# XmasRings.net
KiCad netlist of a schematic drawn in EAGLE
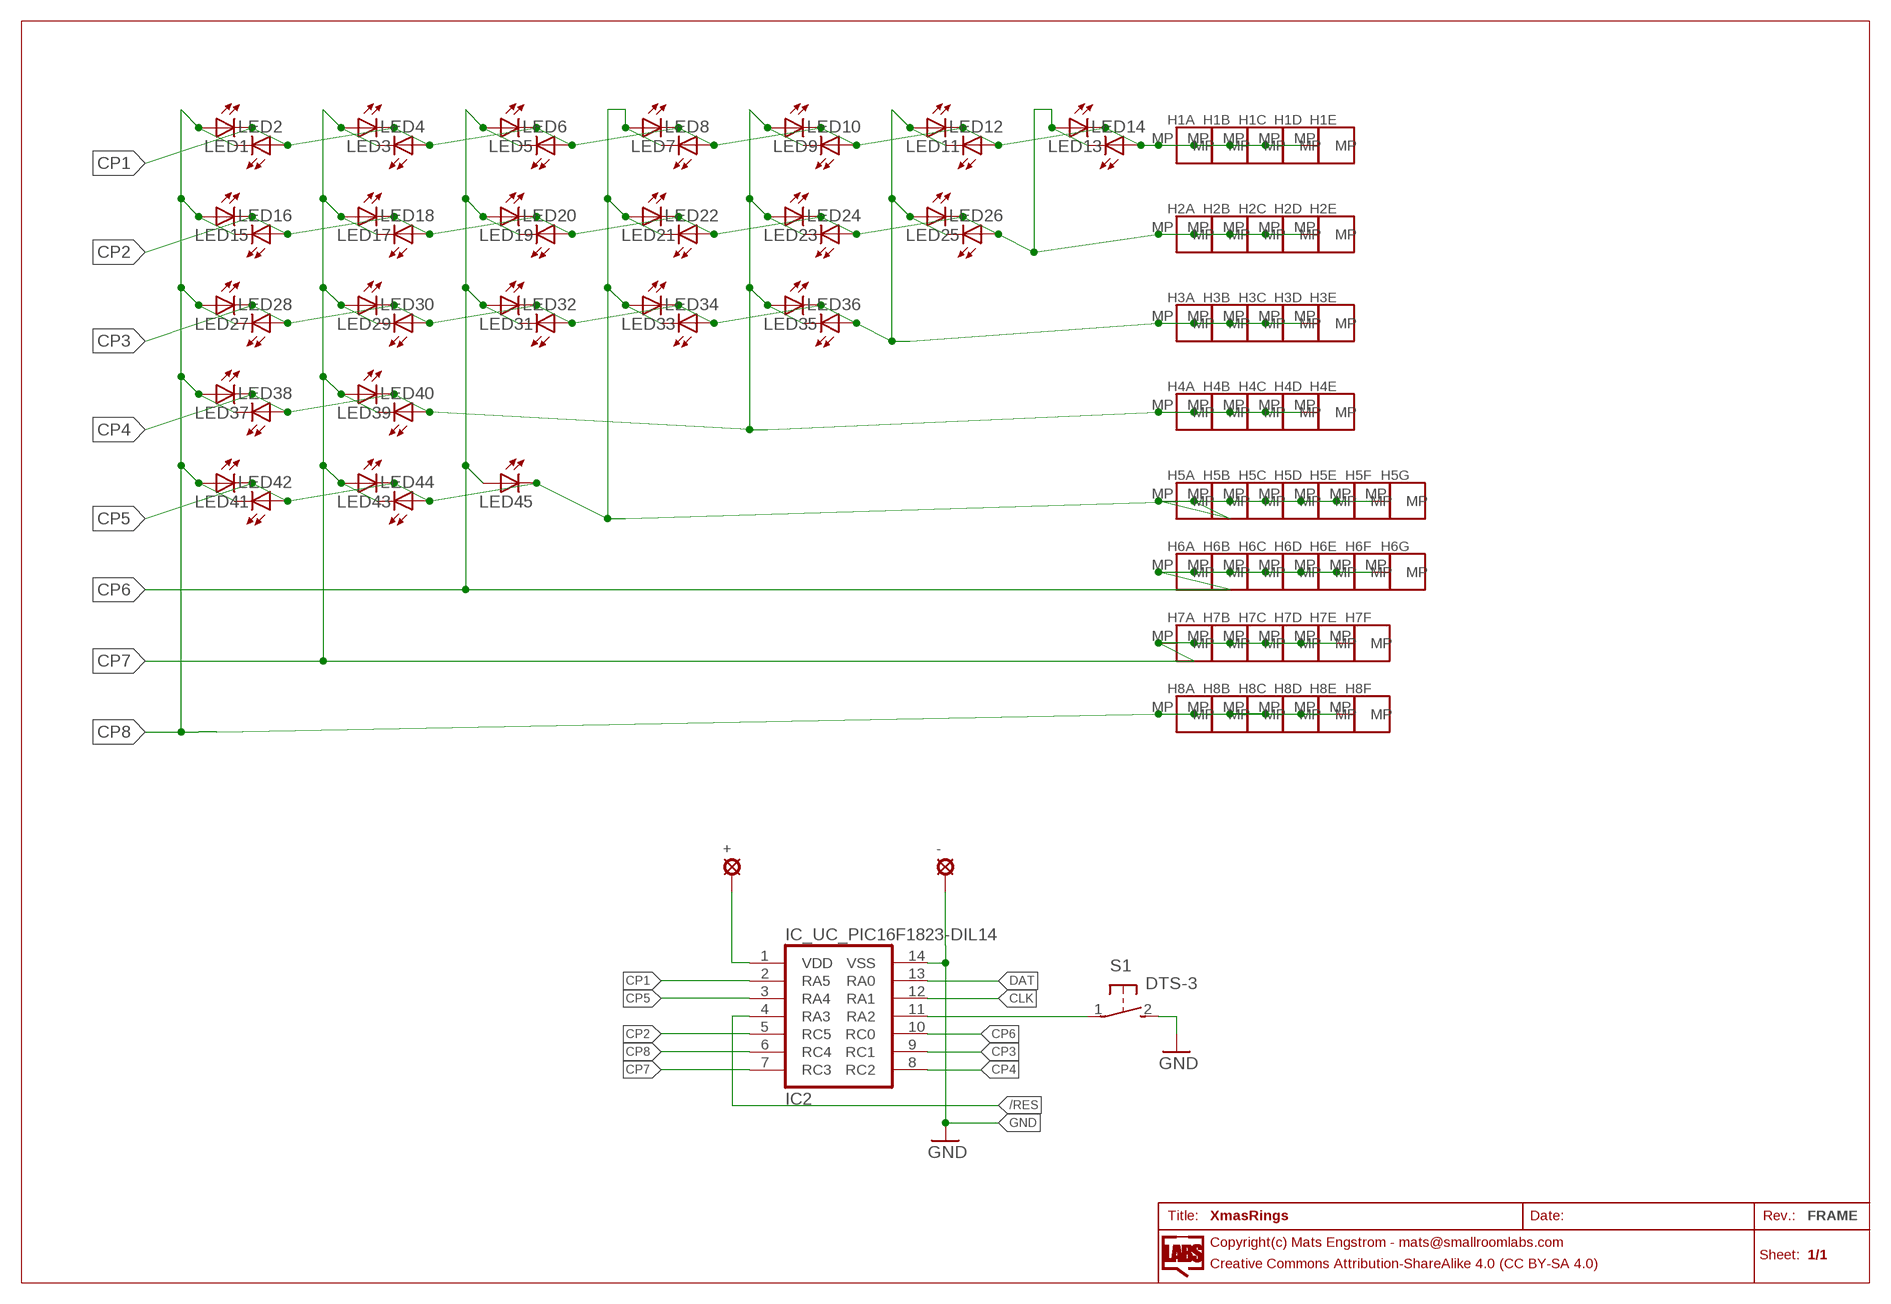
[diagram p0: schematic, sheet 1]

(export (version "E")
  (design (tool "Eeschema 10.0.6"))
  (components
    (comp (ref "+")
      (value "LSP10")
      (footprint "eagle-import:LSP10")
      (libsource (lib "eagle-import") (part "LSP10"))
    )
    (comp (ref "-")
      (value "LSP10")
      (footprint "eagle-import:LSP10")
      (libsource (lib "eagle-import") (part "LSP10"))
    )
    (comp (ref "H1A")
      (value "PADH08SS")
      (footprint "eagle-import:PAD08SS")
      (libsource (lib "eagle-import") (part "PADH08SS"))
    )
    (comp (ref "H1B")
      (value "PADH08SS")
      (footprint "eagle-import:PAD08SS")
      (libsource (lib "eagle-import") (part "PADH08SS"))
    )
    (comp (ref "H1C")
      (value "PADH08SS")
      (footprint "eagle-import:PAD08SS")
      (libsource (lib "eagle-import") (part "PADH08SS"))
    )
    (comp (ref "H1D")
      (value "PADH08SS")
      (footprint "eagle-import:PAD08SS")
      (libsource (lib "eagle-import") (part "PADH08SS"))
    )
    (comp (ref "H1E")
      (value "PADH08SS")
      (footprint "eagle-import:PAD08SS")
      (libsource (lib "eagle-import") (part "PADH08SS"))
    )
    (comp (ref "H2A")
      (value "PADH08SS")
      (footprint "eagle-import:PAD08SS")
      (libsource (lib "eagle-import") (part "PADH08SS"))
    )
    (comp (ref "H2B")
      (value "PADH08SS")
      (footprint "eagle-import:PAD08SS")
      (libsource (lib "eagle-import") (part "PADH08SS"))
    )
    (comp (ref "H2C")
      (value "PADH08SS")
      (footprint "eagle-import:PAD08SS")
      (libsource (lib "eagle-import") (part "PADH08SS"))
    )
    (comp (ref "H2D")
      (value "PADH08SS")
      (footprint "eagle-import:PAD08SS")
      (libsource (lib "eagle-import") (part "PADH08SS"))
    )
    (comp (ref "H2E")
      (value "PADH08SS")
      (footprint "eagle-import:PAD08SS")
      (libsource (lib "eagle-import") (part "PADH08SS"))
    )
    (comp (ref "H3A")
      (value "PADH08SS")
      (footprint "eagle-import:PAD08SS")
      (libsource (lib "eagle-import") (part "PADH08SS"))
    )
    (comp (ref "H3B")
      (value "PADH08SS")
      (footprint "eagle-import:PAD08SS")
      (libsource (lib "eagle-import") (part "PADH08SS"))
    )
    (comp (ref "H3C")
      (value "PADH08SS")
      (footprint "eagle-import:PAD08SS")
      (libsource (lib "eagle-import") (part "PADH08SS"))
    )
    (comp (ref "H3D")
      (value "PADH08SS")
      (footprint "eagle-import:PAD08SS")
      (libsource (lib "eagle-import") (part "PADH08SS"))
    )
    (comp (ref "H3E")
      (value "PADH08SS")
      (footprint "eagle-import:PAD08SS")
      (libsource (lib "eagle-import") (part "PADH08SS"))
    )
    (comp (ref "H4A")
      (value "PADH08SS")
      (footprint "eagle-import:PAD08SS")
      (libsource (lib "eagle-import") (part "PADH08SS"))
    )
    (comp (ref "H4B")
      (value "PADH08SS")
      (footprint "eagle-import:PAD08SS")
      (libsource (lib "eagle-import") (part "PADH08SS"))
    )
    (comp (ref "H4C")
      (value "PADH08SS")
      (footprint "eagle-import:PAD08SS")
      (libsource (lib "eagle-import") (part "PADH08SS"))
    )
    (comp (ref "H4D")
      (value "PADH08SS")
      (footprint "eagle-import:PAD08SS")
      (libsource (lib "eagle-import") (part "PADH08SS"))
    )
    (comp (ref "H4E")
      (value "PADH08SS")
      (footprint "eagle-import:PAD08SS")
      (libsource (lib "eagle-import") (part "PADH08SS"))
    )
    (comp (ref "H5A")
      (value "PADH08SS")
      (footprint "eagle-import:PAD08SS")
      (libsource (lib "eagle-import") (part "PADH08SS"))
    )
    (comp (ref "H5B")
      (value "PADH08SS")
      (footprint "eagle-import:PAD08SS")
      (libsource (lib "eagle-import") (part "PADH08SS"))
    )
    (comp (ref "H5C")
      (value "PADH08SS")
      (footprint "eagle-import:PAD08SS")
      (libsource (lib "eagle-import") (part "PADH08SS"))
    )
    (comp (ref "H5D")
      (value "PADH08SS")
      (footprint "eagle-import:PAD08SS")
      (libsource (lib "eagle-import") (part "PADH08SS"))
    )
    (comp (ref "H5E")
      (value "PADH08SS")
      (footprint "eagle-import:PAD08SS")
      (libsource (lib "eagle-import") (part "PADH08SS"))
    )
    (comp (ref "H5F")
      (value "PADH08SS")
      (footprint "eagle-import:PAD08SS")
      (libsource (lib "eagle-import") (part "PADH08SS"))
    )
    (comp (ref "H5G")
      (value "PADH08SS")
      (footprint "eagle-import:PAD08SS")
      (libsource (lib "eagle-import") (part "PADH08SS"))
    )
    (comp (ref "H6A")
      (value "PADH08SS")
      (footprint "eagle-import:PAD08SS")
      (libsource (lib "eagle-import") (part "PADH08SS"))
    )
    (comp (ref "H6B")
      (value "PADH08SS")
      (footprint "eagle-import:PAD08SS")
      (libsource (lib "eagle-import") (part "PADH08SS"))
    )
    (comp (ref "H6C")
      (value "PADH08SS")
      (footprint "eagle-import:PAD08SS")
      (libsource (lib "eagle-import") (part "PADH08SS"))
    )
    (comp (ref "H6D")
      (value "PADH08SS")
      (footprint "eagle-import:PAD08SS")
      (libsource (lib "eagle-import") (part "PADH08SS"))
    )
    (comp (ref "H6E")
      (value "PADH08SS")
      (footprint "eagle-import:PAD08SS")
      (libsource (lib "eagle-import") (part "PADH08SS"))
    )
    (comp (ref "H6F")
      (value "PADH08SS")
      (footprint "eagle-import:PAD08SS")
      (libsource (lib "eagle-import") (part "PADH08SS"))
    )
    (comp (ref "H6G")
      (value "PADH08SS")
      (footprint "eagle-import:PAD08SS")
      (libsource (lib "eagle-import") (part "PADH08SS"))
    )
    (comp (ref "H7A")
      (value "PADH08SS")
      (footprint "eagle-import:PAD08SS")
      (libsource (lib "eagle-import") (part "PADH08SS"))
    )
    (comp (ref "H7B")
      (value "PADH08SS")
      (footprint "eagle-import:PAD08SS")
      (libsource (lib "eagle-import") (part "PADH08SS"))
    )
    (comp (ref "H7C")
      (value "PADH08SS")
      (footprint "eagle-import:PAD08SS")
      (libsource (lib "eagle-import") (part "PADH08SS"))
    )
    (comp (ref "H7D")
      (value "PADH08SS")
      (footprint "eagle-import:PAD08SS")
      (libsource (lib "eagle-import") (part "PADH08SS"))
    )
    (comp (ref "H7E")
      (value "PADH08SS")
      (footprint "eagle-import:PAD08SS")
      (libsource (lib "eagle-import") (part "PADH08SS"))
    )
    (comp (ref "H7F")
      (value "PADH08SS")
      (footprint "eagle-import:PAD08SS")
      (libsource (lib "eagle-import") (part "PADH08SS"))
    )
    (comp (ref "H8A")
      (value "PADH08SS")
      (footprint "eagle-import:PAD08SS")
      (libsource (lib "eagle-import") (part "PADH08SS"))
    )
    (comp (ref "H8B")
      (value "PADH08SS")
      (footprint "eagle-import:PAD08SS")
      (libsource (lib "eagle-import") (part "PADH08SS"))
    )
    (comp (ref "H8C")
      (value "PADH08SS")
      (footprint "eagle-import:PAD08SS")
      (libsource (lib "eagle-import") (part "PADH08SS"))
    )
    (comp (ref "H8D")
      (value "PADH08SS")
      (footprint "eagle-import:PAD08SS")
      (libsource (lib "eagle-import") (part "PADH08SS"))
    )
    (comp (ref "H8E")
      (value "PADH08SS")
      (footprint "eagle-import:PAD08SS")
      (libsource (lib "eagle-import") (part "PADH08SS"))
    )
    (comp (ref "H8F")
      (value "PADH08SS")
      (footprint "eagle-import:PAD08SS")
      (libsource (lib "eagle-import") (part "PADH08SS"))
    )
    (comp (ref "IC2")
      (value "IC_UC_PIC16F1823-DIL14")
      (footprint "eagle-import:DIP14")
      (libsource (lib "eagle-import") (part "IC_UC_PIC16F1823-DIL14"))
    )
    (comp (ref "LED1")
      (value "LED5SQ")
      (footprint "eagle-import:5MM-SQ")
      (libsource (lib "eagle-import") (part "LED5SQ"))
    )
    (comp (ref "LED2")
      (value "LED5SQ")
      (footprint "eagle-import:5MM-SQ")
      (libsource (lib "eagle-import") (part "LED5SQ"))
    )
    (comp (ref "LED3")
      (value "LED5SQ")
      (footprint "eagle-import:5MM-SQ")
      (libsource (lib "eagle-import") (part "LED5SQ"))
    )
    (comp (ref "LED4")
      (value "LED5SQ")
      (footprint "eagle-import:5MM-SQ")
      (libsource (lib "eagle-import") (part "LED5SQ"))
    )
    (comp (ref "LED5")
      (value "LED5SQ")
      (footprint "eagle-import:5MM-SQ")
      (libsource (lib "eagle-import") (part "LED5SQ"))
    )
    (comp (ref "LED6")
      (value "LED5SQ")
      (footprint "eagle-import:5MM-SQ")
      (libsource (lib "eagle-import") (part "LED5SQ"))
    )
    (comp (ref "LED7")
      (value "LED5SQ")
      (footprint "eagle-import:5MM-SQ")
      (libsource (lib "eagle-import") (part "LED5SQ"))
    )
    (comp (ref "LED8")
      (value "LED5SQ")
      (footprint "eagle-import:5MM-SQ")
      (libsource (lib "eagle-import") (part "LED5SQ"))
    )
    (comp (ref "LED9")
      (value "LED5SQ")
      (footprint "eagle-import:5MM-SQ")
      (libsource (lib "eagle-import") (part "LED5SQ"))
    )
    (comp (ref "LED10")
      (value "LED5SQ")
      (footprint "eagle-import:5MM-SQ")
      (libsource (lib "eagle-import") (part "LED5SQ"))
    )
    (comp (ref "LED11")
      (value "LED5SQ")
      (footprint "eagle-import:5MM-SQ")
      (libsource (lib "eagle-import") (part "LED5SQ"))
    )
    (comp (ref "LED12")
      (value "LED5SQ")
      (footprint "eagle-import:5MM-SQ")
      (libsource (lib "eagle-import") (part "LED5SQ"))
    )
    (comp (ref "LED13")
      (value "LED5SQ")
      (footprint "eagle-import:5MM-SQ")
      (libsource (lib "eagle-import") (part "LED5SQ"))
    )
    (comp (ref "LED14")
      (value "LED5SQ")
      (footprint "eagle-import:5MM-SQ")
      (libsource (lib "eagle-import") (part "LED5SQ"))
    )
    (comp (ref "LED15")
      (value "LED5SQ")
      (footprint "eagle-import:5MM-SQ")
      (libsource (lib "eagle-import") (part "LED5SQ"))
    )
    (comp (ref "LED16")
      (value "LED5SQ")
      (footprint "eagle-import:5MM-SQ")
      (libsource (lib "eagle-import") (part "LED5SQ"))
    )
    (comp (ref "LED17")
      (value "LED5SQ")
      (footprint "eagle-import:5MM-SQ")
      (libsource (lib "eagle-import") (part "LED5SQ"))
    )
    (comp (ref "LED18")
      (value "LED5SQ")
      (footprint "eagle-import:5MM-SQ")
      (libsource (lib "eagle-import") (part "LED5SQ"))
    )
    (comp (ref "LED19")
      (value "LED5SQ")
      (footprint "eagle-import:5MM-SQ")
      (libsource (lib "eagle-import") (part "LED5SQ"))
    )
    (comp (ref "LED20")
      (value "LED5SQ")
      (footprint "eagle-import:5MM-SQ")
      (libsource (lib "eagle-import") (part "LED5SQ"))
    )
    (comp (ref "LED21")
      (value "LED5SQ")
      (footprint "eagle-import:5MM-SQ")
      (libsource (lib "eagle-import") (part "LED5SQ"))
    )
    (comp (ref "LED22")
      (value "LED5SQ")
      (footprint "eagle-import:5MM-SQ")
      (libsource (lib "eagle-import") (part "LED5SQ"))
    )
    (comp (ref "LED23")
      (value "LED5SQ")
      (footprint "eagle-import:5MM-SQ")
      (libsource (lib "eagle-import") (part "LED5SQ"))
    )
    (comp (ref "LED24")
      (value "LED5SQ")
      (footprint "eagle-import:5MM-SQ")
      (libsource (lib "eagle-import") (part "LED5SQ"))
    )
    (comp (ref "LED25")
      (value "LED5SQ")
      (footprint "eagle-import:5MM-SQ")
      (libsource (lib "eagle-import") (part "LED5SQ"))
    )
    (comp (ref "LED26")
      (value "LED5SQ")
      (footprint "eagle-import:5MM-SQ")
      (libsource (lib "eagle-import") (part "LED5SQ"))
    )
    (comp (ref "LED27")
      (value "LED5SQ")
      (footprint "eagle-import:5MM-SQ")
      (libsource (lib "eagle-import") (part "LED5SQ"))
    )
    (comp (ref "LED28")
      (value "LED5SQ")
      (footprint "eagle-import:5MM-SQ")
      (libsource (lib "eagle-import") (part "LED5SQ"))
    )
    (comp (ref "LED29")
      (value "LED5SQ")
      (footprint "eagle-import:5MM-SQ")
      (libsource (lib "eagle-import") (part "LED5SQ"))
    )
    (comp (ref "LED30")
      (value "LED5SQ")
      (footprint "eagle-import:5MM-SQ")
      (libsource (lib "eagle-import") (part "LED5SQ"))
    )
    (comp (ref "LED31")
      (value "LED5SQ")
      (footprint "eagle-import:5MM-SQ")
      (libsource (lib "eagle-import") (part "LED5SQ"))
    )
    (comp (ref "LED32")
      (value "LED5SQ")
      (footprint "eagle-import:5MM-SQ")
      (libsource (lib "eagle-import") (part "LED5SQ"))
    )
    (comp (ref "LED33")
      (value "LED5SQ")
      (footprint "eagle-import:5MM-SQ")
      (libsource (lib "eagle-import") (part "LED5SQ"))
    )
    (comp (ref "LED34")
      (value "LED5SQ")
      (footprint "eagle-import:5MM-SQ")
      (libsource (lib "eagle-import") (part "LED5SQ"))
    )
    (comp (ref "LED35")
      (value "LED5SQ")
      (footprint "eagle-import:5MM-SQ")
      (libsource (lib "eagle-import") (part "LED5SQ"))
    )
    (comp (ref "LED36")
      (value "LED5SQ")
      (footprint "eagle-import:5MM-SQ")
      (libsource (lib "eagle-import") (part "LED5SQ"))
    )
    (comp (ref "LED37")
      (value "LED5SQ")
      (footprint "eagle-import:5MM-SQ")
      (libsource (lib "eagle-import") (part "LED5SQ"))
    )
    (comp (ref "LED38")
      (value "LED5SQ")
      (footprint "eagle-import:5MM-SQ")
      (libsource (lib "eagle-import") (part "LED5SQ"))
    )
    (comp (ref "LED39")
      (value "LED5SQ")
      (footprint "eagle-import:5MM-SQ")
      (libsource (lib "eagle-import") (part "LED5SQ"))
    )
    (comp (ref "LED40")
      (value "LED5SQ")
      (footprint "eagle-import:5MM-SQ")
      (libsource (lib "eagle-import") (part "LED5SQ"))
    )
    (comp (ref "LED41")
      (value "LED5SQ")
      (footprint "eagle-import:5MM-SQ")
      (libsource (lib "eagle-import") (part "LED5SQ"))
    )
    (comp (ref "LED42")
      (value "LED5SQ")
      (footprint "eagle-import:5MM-SQ")
      (libsource (lib "eagle-import") (part "LED5SQ"))
    )
    (comp (ref "LED43")
      (value "LED5SQ")
      (footprint "eagle-import:5MM-SQ")
      (libsource (lib "eagle-import") (part "LED5SQ"))
    )
    (comp (ref "LED44")
      (value "LED5SQ")
      (footprint "eagle-import:5MM-SQ")
      (libsource (lib "eagle-import") (part "LED5SQ"))
    )
    (comp (ref "LED45")
      (value "LED5SQ")
      (footprint "eagle-import:5MM-SQ")
      (libsource (lib "eagle-import") (part "LED5SQ"))
    )
    (comp (ref "S1")
      (value "DTS-3")
      (footprint "eagle-import:DTS-3")
      (libsource (lib "eagle-import") (part "DTS-3"))
    )
  )
  (nets
    (net (code "1") (name "CLK") (class "Default")
      (node (ref "IC2") (pin "12") (pinfunction "RA1_12") (pintype "bidirectional"))
    )
    (net (code "2") (name "CP1") (class "Default")
      (node (ref "H1A") (pin "MP") (pinfunction "MP_MP") (pintype "passive"))
      (node (ref "H1B") (pin "MP") (pinfunction "MP_MP") (pintype "passive"))
      (node (ref "H1C") (pin "MP") (pinfunction "MP_MP") (pintype "passive"))
      (node (ref "H1D") (pin "MP") (pinfunction "MP_MP") (pintype "passive"))
      (node (ref "H1E") (pin "MP") (pinfunction "MP_MP") (pintype "passive"))
      (node (ref "IC2") (pin "2") (pinfunction "RA5_2") (pintype "bidirectional"))
      (node (ref "LED1") (pin "C") (pinfunction "C_C") (pintype "bidirectional"))
      (node (ref "LED10") (pin "A") (pinfunction "A_A") (pintype "bidirectional"))
      (node (ref "LED11") (pin "C") (pinfunction "C_C") (pintype "bidirectional"))
      (node (ref "LED12") (pin "A") (pinfunction "A_A") (pintype "bidirectional"))
      (node (ref "LED13") (pin "C") (pinfunction "C_C") (pintype "bidirectional"))
      (node (ref "LED14") (pin "A") (pinfunction "A_A") (pintype "bidirectional"))
      (node (ref "LED2") (pin "A") (pinfunction "A_A") (pintype "bidirectional"))
      (node (ref "LED3") (pin "C") (pinfunction "C_C") (pintype "bidirectional"))
      (node (ref "LED4") (pin "A") (pinfunction "A_A") (pintype "bidirectional"))
      (node (ref "LED5") (pin "C") (pinfunction "C_C") (pintype "bidirectional"))
      (node (ref "LED6") (pin "A") (pinfunction "A_A") (pintype "bidirectional"))
      (node (ref "LED7") (pin "C") (pinfunction "C_C") (pintype "bidirectional"))
      (node (ref "LED8") (pin "A") (pinfunction "A_A") (pintype "bidirectional"))
      (node (ref "LED9") (pin "C") (pinfunction "C_C") (pintype "bidirectional"))
    )
    (net (code "3") (name "CP2") (class "Default")
      (node (ref "H2A") (pin "MP") (pinfunction "MP_MP") (pintype "passive"))
      (node (ref "H2B") (pin "MP") (pinfunction "MP_MP") (pintype "passive"))
      (node (ref "H2C") (pin "MP") (pinfunction "MP_MP") (pintype "passive"))
      (node (ref "H2D") (pin "MP") (pinfunction "MP_MP") (pintype "passive"))
      (node (ref "H2E") (pin "MP") (pinfunction "MP_MP") (pintype "passive"))
      (node (ref "IC2") (pin "5") (pinfunction "RC5_5") (pintype "bidirectional"))
      (node (ref "LED13") (pin "A") (pinfunction "A_A") (pintype "bidirectional"))
      (node (ref "LED14") (pin "C") (pinfunction "C_C") (pintype "bidirectional"))
      (node (ref "LED15") (pin "C") (pinfunction "C_C") (pintype "bidirectional"))
      (node (ref "LED16") (pin "A") (pinfunction "A_A") (pintype "bidirectional"))
      (node (ref "LED17") (pin "C") (pinfunction "C_C") (pintype "bidirectional"))
      (node (ref "LED18") (pin "A") (pinfunction "A_A") (pintype "bidirectional"))
      (node (ref "LED19") (pin "C") (pinfunction "C_C") (pintype "bidirectional"))
      (node (ref "LED20") (pin "A") (pinfunction "A_A") (pintype "bidirectional"))
      (node (ref "LED21") (pin "C") (pinfunction "C_C") (pintype "bidirectional"))
      (node (ref "LED22") (pin "A") (pinfunction "A_A") (pintype "bidirectional"))
      (node (ref "LED23") (pin "C") (pinfunction "C_C") (pintype "bidirectional"))
      (node (ref "LED24") (pin "A") (pinfunction "A_A") (pintype "bidirectional"))
      (node (ref "LED25") (pin "C") (pinfunction "C_C") (pintype "bidirectional"))
      (node (ref "LED26") (pin "A") (pinfunction "A_A") (pintype "bidirectional"))
    )
    (net (code "4") (name "CP3") (class "Default")
      (node (ref "H3A") (pin "MP") (pinfunction "MP_MP") (pintype "passive"))
      (node (ref "H3B") (pin "MP") (pinfunction "MP_MP") (pintype "passive"))
      (node (ref "H3C") (pin "MP") (pinfunction "MP_MP") (pintype "passive"))
      (node (ref "H3D") (pin "MP") (pinfunction "MP_MP") (pintype "passive"))
      (node (ref "H3E") (pin "MP") (pinfunction "MP_MP") (pintype "passive"))
      (node (ref "IC2") (pin "9") (pinfunction "RC1_9") (pintype "bidirectional"))
      (node (ref "LED11") (pin "A") (pinfunction "A_A") (pintype "bidirectional"))
      (node (ref "LED12") (pin "C") (pinfunction "C_C") (pintype "bidirectional"))
      (node (ref "LED25") (pin "A") (pinfunction "A_A") (pintype "bidirectional"))
      (node (ref "LED26") (pin "C") (pinfunction "C_C") (pintype "bidirectional"))
      (node (ref "LED27") (pin "C") (pinfunction "C_C") (pintype "bidirectional"))
      (node (ref "LED28") (pin "A") (pinfunction "A_A") (pintype "bidirectional"))
      (node (ref "LED29") (pin "C") (pinfunction "C_C") (pintype "bidirectional"))
      (node (ref "LED30") (pin "A") (pinfunction "A_A") (pintype "bidirectional"))
      (node (ref "LED31") (pin "C") (pinfunction "C_C") (pintype "bidirectional"))
      (node (ref "LED32") (pin "A") (pinfunction "A_A") (pintype "bidirectional"))
      (node (ref "LED33") (pin "C") (pinfunction "C_C") (pintype "bidirectional"))
      (node (ref "LED34") (pin "A") (pinfunction "A_A") (pintype "bidirectional"))
      (node (ref "LED35") (pin "C") (pinfunction "C_C") (pintype "bidirectional"))
      (node (ref "LED36") (pin "A") (pinfunction "A_A") (pintype "bidirectional"))
    )
    (net (code "5") (name "CP4") (class "Default")
      (node (ref "H4A") (pin "MP") (pinfunction "MP_MP") (pintype "passive"))
      (node (ref "H4B") (pin "MP") (pinfunction "MP_MP") (pintype "passive"))
      (node (ref "H4C") (pin "MP") (pinfunction "MP_MP") (pintype "passive"))
      (node (ref "H4D") (pin "MP") (pinfunction "MP_MP") (pintype "passive"))
      (node (ref "H4E") (pin "MP") (pinfunction "MP_MP") (pintype "passive"))
      (node (ref "IC2") (pin "8") (pinfunction "RC2_8") (pintype "bidirectional"))
      (node (ref "LED10") (pin "C") (pinfunction "C_C") (pintype "bidirectional"))
      (node (ref "LED23") (pin "A") (pinfunction "A_A") (pintype "bidirectional"))
      (node (ref "LED24") (pin "C") (pinfunction "C_C") (pintype "bidirectional"))
      (node (ref "LED35") (pin "A") (pinfunction "A_A") (pintype "bidirectional"))
      (node (ref "LED36") (pin "C") (pinfunction "C_C") (pintype "bidirectional"))
      (node (ref "LED37") (pin "C") (pinfunction "C_C") (pintype "bidirectional"))
      (node (ref "LED38") (pin "A") (pinfunction "A_A") (pintype "bidirectional"))
      (node (ref "LED39") (pin "C") (pinfunction "C_C") (pintype "bidirectional"))
      (node (ref "LED40") (pin "A") (pinfunction "A_A") (pintype "bidirectional"))
      (node (ref "LED9") (pin "A") (pinfunction "A_A") (pintype "bidirectional"))
    )
    (net (code "6") (name "CP5") (class "Default")
      (node (ref "H5A") (pin "MP") (pinfunction "MP_MP") (pintype "passive"))
      (node (ref "H5B") (pin "MP") (pinfunction "MP_MP") (pintype "passive"))
      (node (ref "H5C") (pin "MP") (pinfunction "MP_MP") (pintype "passive"))
      (node (ref "H5D") (pin "MP") (pinfunction "MP_MP") (pintype "passive"))
      (node (ref "H5E") (pin "MP") (pinfunction "MP_MP") (pintype "passive"))
      (node (ref "H5F") (pin "MP") (pinfunction "MP_MP") (pintype "passive"))
      (node (ref "H5G") (pin "MP") (pinfunction "MP_MP") (pintype "passive"))
      (node (ref "IC2") (pin "3") (pinfunction "RA4_3") (pintype "bidirectional"))
      (node (ref "LED21") (pin "A") (pinfunction "A_A") (pintype "bidirectional"))
      (node (ref "LED22") (pin "C") (pinfunction "C_C") (pintype "bidirectional"))
      (node (ref "LED33") (pin "A") (pinfunction "A_A") (pintype "bidirectional"))
      (node (ref "LED34") (pin "C") (pinfunction "C_C") (pintype "bidirectional"))
      (node (ref "LED41") (pin "C") (pinfunction "C_C") (pintype "bidirectional"))
      (node (ref "LED42") (pin "A") (pinfunction "A_A") (pintype "bidirectional"))
      (node (ref "LED43") (pin "C") (pinfunction "C_C") (pintype "bidirectional"))
      (node (ref "LED44") (pin "A") (pinfunction "A_A") (pintype "bidirectional"))
      (node (ref "LED45") (pin "C") (pinfunction "C_C") (pintype "bidirectional"))
      (node (ref "LED7") (pin "A") (pinfunction "A_A") (pintype "bidirectional"))
      (node (ref "LED8") (pin "C") (pinfunction "C_C") (pintype "bidirectional"))
    )
    (net (code "7") (name "CP6") (class "Default")
      (node (ref "H6A") (pin "MP") (pinfunction "MP_MP") (pintype "passive"))
      (node (ref "H6B") (pin "MP") (pinfunction "MP_MP") (pintype "passive"))
      (node (ref "H6C") (pin "MP") (pinfunction "MP_MP") (pintype "passive"))
      (node (ref "H6D") (pin "MP") (pinfunction "MP_MP") (pintype "passive"))
      (node (ref "H6E") (pin "MP") (pinfunction "MP_MP") (pintype "passive"))
      (node (ref "H6F") (pin "MP") (pinfunction "MP_MP") (pintype "passive"))
      (node (ref "H6G") (pin "MP") (pinfunction "MP_MP") (pintype "passive"))
      (node (ref "IC2") (pin "10") (pinfunction "RC0_10") (pintype "bidirectional"))
      (node (ref "LED19") (pin "A") (pinfunction "A_A") (pintype "bidirectional"))
      (node (ref "LED20") (pin "C") (pinfunction "C_C") (pintype "bidirectional"))
      (node (ref "LED31") (pin "A") (pinfunction "A_A") (pintype "bidirectional"))
      (node (ref "LED32") (pin "C") (pinfunction "C_C") (pintype "bidirectional"))
      (node (ref "LED45") (pin "A") (pinfunction "A_A") (pintype "bidirectional"))
      (node (ref "LED5") (pin "A") (pinfunction "A_A") (pintype "bidirectional"))
      (node (ref "LED6") (pin "C") (pinfunction "C_C") (pintype "bidirectional"))
    )
    (net (code "8") (name "CP7") (class "Default")
      (node (ref "H7A") (pin "MP") (pinfunction "MP_MP") (pintype "passive"))
      (node (ref "H7B") (pin "MP") (pinfunction "MP_MP") (pintype "passive"))
      (node (ref "H7C") (pin "MP") (pinfunction "MP_MP") (pintype "passive"))
      (node (ref "H7D") (pin "MP") (pinfunction "MP_MP") (pintype "passive"))
      (node (ref "H7E") (pin "MP") (pinfunction "MP_MP") (pintype "passive"))
      (node (ref "H7F") (pin "MP") (pinfunction "MP_MP") (pintype "passive"))
      (node (ref "IC2") (pin "7") (pinfunction "RC3_7") (pintype "bidirectional"))
      (node (ref "LED17") (pin "A") (pinfunction "A_A") (pintype "bidirectional"))
      (node (ref "LED18") (pin "C") (pinfunction "C_C") (pintype "bidirectional"))
      (node (ref "LED29") (pin "A") (pinfunction "A_A") (pintype "bidirectional"))
      (node (ref "LED3") (pin "A") (pinfunction "A_A") (pintype "bidirectional"))
      (node (ref "LED30") (pin "C") (pinfunction "C_C") (pintype "bidirectional"))
      (node (ref "LED39") (pin "A") (pinfunction "A_A") (pintype "bidirectional"))
      (node (ref "LED4") (pin "C") (pinfunction "C_C") (pintype "bidirectional"))
      (node (ref "LED40") (pin "C") (pinfunction "C_C") (pintype "bidirectional"))
      (node (ref "LED43") (pin "A") (pinfunction "A_A") (pintype "bidirectional"))
      (node (ref "LED44") (pin "C") (pinfunction "C_C") (pintype "bidirectional"))
    )
    (net (code "9") (name "CP8") (class "Default")
      (node (ref "H8A") (pin "MP") (pinfunction "MP_MP") (pintype "passive"))
      (node (ref "H8B") (pin "MP") (pinfunction "MP_MP") (pintype "passive"))
      (node (ref "H8C") (pin "MP") (pinfunction "MP_MP") (pintype "passive"))
      (node (ref "H8D") (pin "MP") (pinfunction "MP_MP") (pintype "passive"))
      (node (ref "H8E") (pin "MP") (pinfunction "MP_MP") (pintype "passive"))
      (node (ref "H8F") (pin "MP") (pinfunction "MP_MP") (pintype "passive"))
      (node (ref "IC2") (pin "6") (pinfunction "RC4_6") (pintype "bidirectional"))
      (node (ref "LED1") (pin "A") (pinfunction "A_A") (pintype "bidirectional"))
      (node (ref "LED15") (pin "A") (pinfunction "A_A") (pintype "bidirectional"))
      (node (ref "LED16") (pin "C") (pinfunction "C_C") (pintype "bidirectional"))
      (node (ref "LED2") (pin "C") (pinfunction "C_C") (pintype "bidirectional"))
      (node (ref "LED27") (pin "A") (pinfunction "A_A") (pintype "bidirectional"))
      (node (ref "LED28") (pin "C") (pinfunction "C_C") (pintype "bidirectional"))
      (node (ref "LED37") (pin "A") (pinfunction "A_A") (pintype "bidirectional"))
      (node (ref "LED38") (pin "C") (pinfunction "C_C") (pintype "bidirectional"))
      (node (ref "LED41") (pin "A") (pinfunction "A_A") (pintype "bidirectional"))
      (node (ref "LED42") (pin "C") (pinfunction "C_C") (pintype "bidirectional"))
    )
    (net (code "10") (name "DAT") (class "Default")
      (node (ref "IC2") (pin "13") (pinfunction "RA0_13") (pintype "bidirectional"))
    )
    (net (code "11") (name "GND") (class "Default")
      (node (ref "-") (pin "MP") (pinfunction "MP_MP") (pintype "passive"))
      (node (ref "IC2") (pin "14") (pinfunction "VSS_14") (pintype "power_in"))
      (node (ref "S1") (pin "2") (pinfunction "2_2") (pintype "passive"))
    )
    (net (code "12") (name "Net-(IC2-RA2)") (class "Default")
      (node (ref "IC2") (pin "11") (pinfunction "RA2_11") (pintype "bidirectional"))
      (node (ref "S1") (pin "1") (pinfunction "1_1") (pintype "passive"))
    )
    (net (code "13") (name "Net-(IC2-VDD)") (class "Default")
      (node (ref "+") (pin "MP") (pinfunction "MP_MP") (pintype "passive"))
      (node (ref "IC2") (pin "1") (pinfunction "VDD_1") (pintype "power_in"))
    )
    (net (code "14") (name "{slash}RES") (class "Default")
      (node (ref "IC2") (pin "4") (pinfunction "RA3_4") (pintype "bidirectional"))
    )
  )
)
